# Sensor.net
KiCad netlist of a schematic drawn in Altium Designer
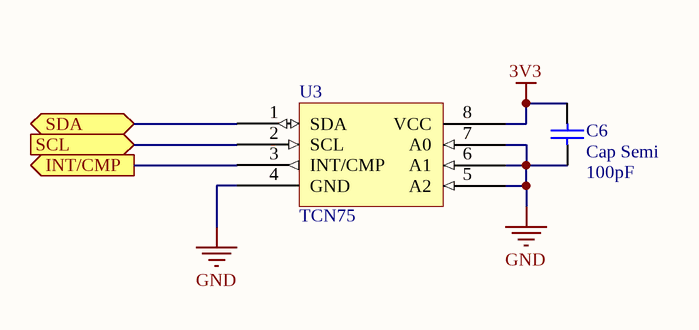
[diagram p0: Sensor.SchDoc]

(export (version "E")
  (design (tool "Eeschema 10.0.6"))
  (components
    (comp (ref "C6")
      (value "Cap Semi")
      (footprint "1608[0603]")
      (description "Capacitor (Semiconductor SIM Model)")
      (fields (field (name "ALTIUM_VALUE") "100pF") (field (name "PUBLISHER") "Altium Limited"))
      (libsource (lib "Miscellaneous Devices") (part "Cap Semi"))
    )
    (comp (ref "U3")
      (value "TCN75")
      (footprint "TCN75-SOIC")
      (description "TCN75数字温度传感器将-40°C到+125°C范围内的温度转换为数字")
      (libsource (lib "ad_test2_IntLib") (part "TCN75"))
    )
  )
  (nets
    (net (code "1") (name "/INT{slash}CMP") (class "Default")
      (node (ref "U3") (pin "3") (pinfunction "INT/CMP_3") (pintype "output"))
    )
    (net (code "2") (name "/SCL") (class "Default")
      (node (ref "U3") (pin "2") (pinfunction "SCL_2") (pintype "input"))
    )
    (net (code "3") (name "/SDA") (class "Default")
      (node (ref "U3") (pin "1") (pinfunction "SDA_1") (pintype "bidirectional"))
    )
    (net (code "4") (name "3V3") (class "Default")
      (node (ref "C6") (pin "2") (pinfunction "2_2") (pintype "passive"))
      (node (ref "U3") (pin "8") (pinfunction "VCC_8") (pintype "power_in"))
    )
    (net (code "5") (name "GND") (class "Default")
      (node (ref "C6") (pin "1") (pinfunction "1_1") (pintype "passive"))
      (node (ref "U3") (pin "4") (pinfunction "GND_4") (pintype "power_in"))
      (node (ref "U3") (pin "5") (pinfunction "A2_5") (pintype "input"))
      (node (ref "U3") (pin "6") (pinfunction "A1_6") (pintype "input"))
      (node (ref "U3") (pin "7") (pinfunction "A0_7") (pintype "input"))
    )
  )
)
